# 780-00020_rev_1_pg1_Two_Axis_Stepper_Dri.net
KiCad netlist of a schematic drawn in Altium Designer
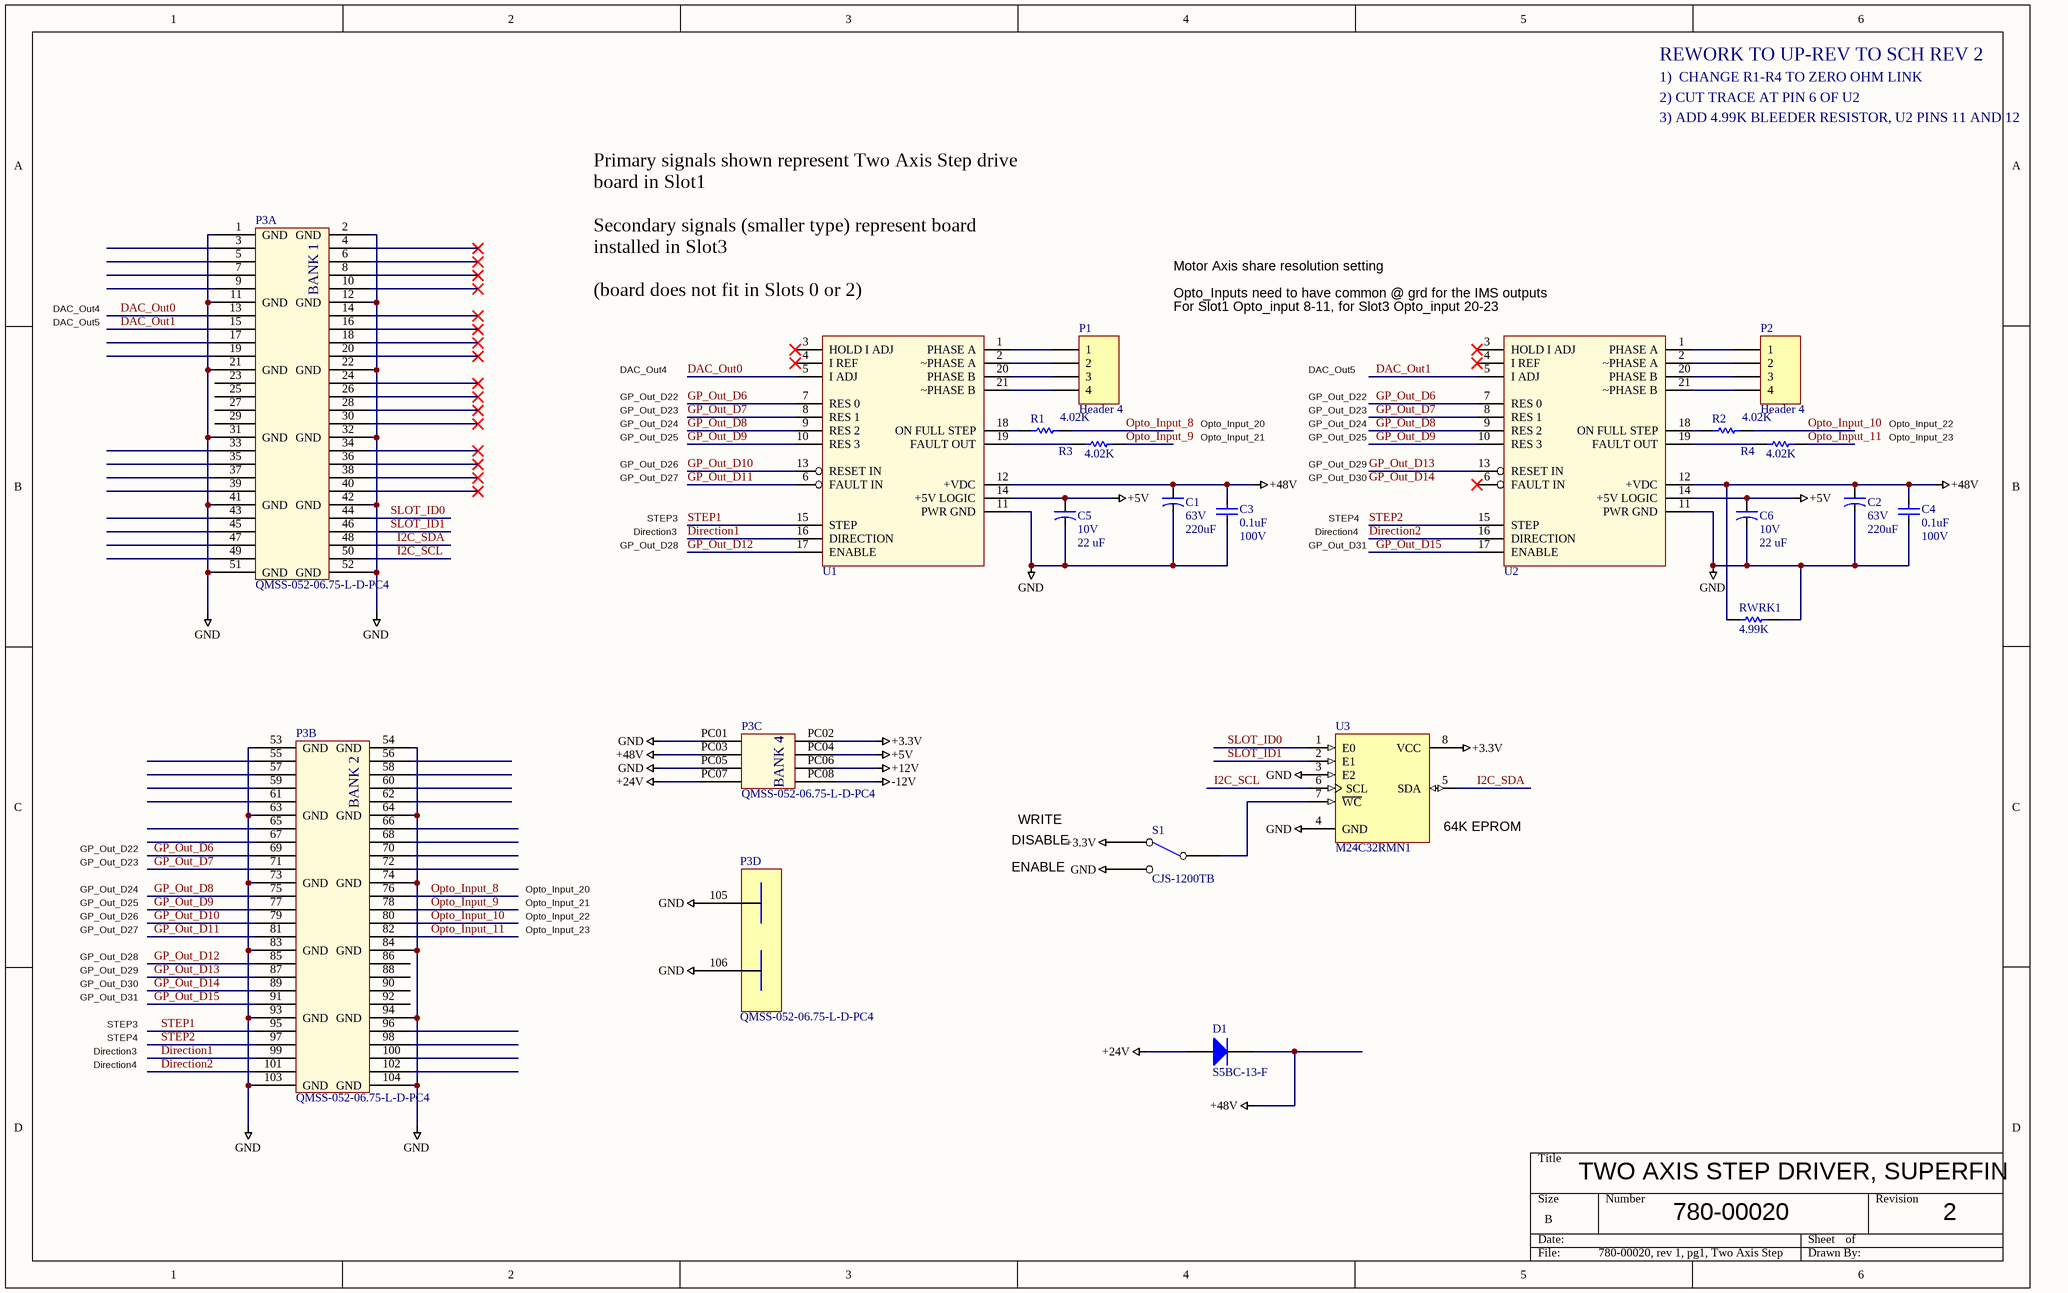
[diagram p0: 780-00020, rev 1, pg1, Two Axis Stepper Driver.SchDoc]

(export (version "E")
  (design (tool "Eeschema 10.0.6"))
  (components
    (comp (ref "C1")
      (value "63V")
      (footprint "CAP 220uF 63V")
      (description "CAP 220UF 63V ELECT MVH SMD")
      (fields (field (name "MANUFACTURER") "United Chemi-Con") (field (name "ALTIUM_VALUE") "220uF"))
      (libsource (lib "Richs Schematic Components") (part "Cap 220uF, 63V"))
    )
    (comp (ref "C2")
      (value "63V")
      (footprint "CAP 220uF 63V")
      (description "CAP 220UF 63V ELECT MVH SMD")
      (fields (field (name "MANUFACTURER") "United Chemi-Con") (field (name "ALTIUM_VALUE") "220uF"))
      (libsource (lib "Richs Schematic Components") (part "Cap 220uF, 63V"))
    )
    (comp (ref "C3")
      (value "100V")
      (footprint "SMD_0805")
      (description "Capacitor")
      (fields (field (name "MANUFACTURER") "TDK") (field (name "ALTIUM_VALUE") "0.1uF"))
      (libsource (lib "Richs Schematic Components") (part "Cap SMD"))
    )
    (comp (ref "C4")
      (value "100V")
      (footprint "SMD_0805")
      (description "Capacitor")
      (fields (field (name "MANUFACTURER") "TDK") (field (name "ALTIUM_VALUE") "0.1uF"))
      (libsource (lib "Richs Schematic Components") (part "Cap SMD"))
    )
    (comp (ref "C5")
      (value "10V")
      (footprint "SMD_CAP_3216")
      (description "outline 3.2mm x 1.6mm")
      (fields (field (name "MANUFACTURER") "AVX") (field (name "ALTIUM_VALUE") "22 uF"))
      (libsource (lib "Richs Schematic Components") (part "Cap Tant 16V"))
    )
    (comp (ref "C6")
      (value "10V")
      (footprint "SMD_CAP_3216")
      (description "outline 3.2mm x 1.6mm")
      (fields (field (name "MANUFACTURER") "AVX") (field (name "ALTIUM_VALUE") "22 uF"))
      (libsource (lib "Richs Schematic Components") (part "Cap Tant 16V"))
    )
    (comp (ref "D1")
      (value "S5BC-13-F")
      (footprint "SMC")
      (description "RECTIFIER GPP SMD 100V 5A SMC")
      (fields (field (name "MANUFACTURER") "Diodes Inc"))
      (libsource (lib "Miscellaneous Devices") (part "Diode"))
    )
    (comp (ref "P1")
      (value "Header 4")
      (footprint "HDR1X4 for IDC")
      (description "Header, 4-Pin")
      (libsource (lib "Richs Schematic Components") (part "Header 4"))
    )
    (comp (ref "P2")
      (value "Header 4")
      (footprint "HDR1X4 for IDC")
      (description "Header, 4-Pin")
      (libsource (lib "Richs Schematic Components") (part "Header 4"))
    )
    (comp (ref "P3")
      (value "QMSS-052-06.75-L-D-PC4")
      (footprint "QMS SMD PWR PINS - 104PIN")
      (description "SAMTEC QMSS W/PWR PINS")
      (fields (field (name "MANUFACTURER") "SAMTEC"))
      (libsource (lib "Richs Schematic Components") (part "QMSS-PC4-104 pin"))
    )
    (comp (ref "R1")
      (value "4.02K")
      (footprint "SMD_0805")
      (description "Resistor 0805")
      (fields (field (name "MANUFACTURER") "Vishay/Dale") (field (name "Comment") "Res 0805"))
      (libsource (lib "Richs Schematic Components") (part "Res SMD"))
    )
    (comp (ref "R2")
      (value "4.02K")
      (footprint "SMD_0805")
      (description "Resistor 0805")
      (fields (field (name "MANUFACTURER") "Vishay/Dale") (field (name "Comment") "Res 0805"))
      (libsource (lib "Richs Schematic Components") (part "Res SMD"))
    )
    (comp (ref "R3")
      (value "4.02K")
      (footprint "SMD_0805")
      (description "Resistor 0805")
      (fields (field (name "MANUFACTURER") "Vishay/Dale") (field (name "Comment") "Res 0805"))
      (libsource (lib "Richs Schematic Components") (part "Res SMD"))
    )
    (comp (ref "R4")
      (value "4.02K")
      (footprint "SMD_0805")
      (description "Resistor 0805")
      (fields (field (name "MANUFACTURER") "Vishay/Dale") (field (name "Comment") "Res 0805"))
      (libsource (lib "Richs Schematic Components") (part "Res SMD"))
    )
    (comp (ref "RWRK1")
      (value "4.99K")
      (footprint "AXIAL-0.4")
      (description "Resistor")
      (fields (field (name "Comment") "Res TH"))
      (libsource (lib "Richs Schematic Components") (part "Res TH"))
    )
    (comp (ref "S1")
      (value "CJS-1200TB")
      (footprint "CAS-120B")
      (fields (field (name "MANUFACTURER") "Copal Electronics"))
      (libsource (lib "JON_1_Library") (part "SW_SPDT_DOUG"))
    )
    (comp (ref "U1")
      (value "IM481H Plus")
      (footprint "IM481H Vertical")
      (description "Hybrid stepper motor driver")
      (libsource (lib "Richs Schematic Components") (part "IM481H Plus"))
    )
    (comp (ref "U2")
      (value "IM481H Plus")
      (footprint "IM481H Vertical")
      (description "Hybrid stepper motor driver")
      (libsource (lib "Richs Schematic Components") (part "IM481H Plus"))
    )
    (comp (ref "U3")
      (value "M24C32RMN1")
      (footprint "SOP8_N")
      (description "32 Kbit Serial I²C Bus EEPROM")
      (libsource (lib "ST Memory EEPROM Serial") (part "M24C32RMN1"))
    )
  )
  (nets
    (net (code "1") (name "+3.3V") (class "Default")
      (node (ref "P3") (pin "PC02") (pinfunction "PC02_PC02") (pintype "passive"))
      (node (ref "S1") (pin "3") (pinfunction "NC_3") (pintype "passive"))
      (node (ref "U3") (pin "8") (pinfunction "VCC_8") (pintype "power_in"))
    )
    (net (code "2") (name "+5V") (class "Default")
      (node (ref "C5") (pin "1") (pinfunction "1_1") (pintype "passive"))
      (node (ref "C6") (pin "1") (pinfunction "1_1") (pintype "passive"))
      (node (ref "P3") (pin "PC04") (pinfunction "PC04_PC04") (pintype "passive"))
      (node (ref "U1") (pin "14") (pinfunction "+5V_LOGIC_14") (pintype "passive"))
      (node (ref "U2") (pin "14") (pinfunction "+5V_LOGIC_14") (pintype "passive"))
    )
    (net (code "3") (name "+12V") (class "Default")
      (node (ref "P3") (pin "PC06") (pinfunction "PC06_PC06") (pintype "passive"))
    )
    (net (code "4") (name "+24V") (class "Default")
      (node (ref "D1") (pin "1") (pinfunction "A_1") (pintype "passive"))
      (node (ref "P3") (pin "PC07") (pinfunction "PC07_PC07") (pintype "passive"))
    )
    (net (code "5") (name "+48V") (class "Default")
      (node (ref "C1") (pin "1") (pinfunction "1_1") (pintype "passive"))
      (node (ref "C2") (pin "1") (pinfunction "1_1") (pintype "passive"))
      (node (ref "C3") (pin "2") (pinfunction "2_2") (pintype "passive"))
      (node (ref "C4") (pin "2") (pinfunction "2_2") (pintype "passive"))
      (node (ref "D1") (pin "2") (pinfunction "K_2") (pintype "passive"))
      (node (ref "P3") (pin "PC03") (pinfunction "PC03_PC03") (pintype "passive"))
      (node (ref "RWRK1") (pin "1") (pinfunction "1_1") (pintype "passive"))
      (node (ref "U1") (pin "12") (pinfunction "+VDC_12") (pintype "passive"))
      (node (ref "U2") (pin "12") (pinfunction "+VDC_12") (pintype "passive"))
    )
    (net (code "6") (name "-12V") (class "Default")
      (node (ref "P3") (pin "PC08") (pinfunction "PC08_PC08") (pintype "passive"))
    )
    (net (code "7") (name "/DAC_Out0") (class "Default")
      (node (ref "P3") (pin "13") (pinfunction "13_13") (pintype "passive"))
      (node (ref "U1") (pin "5") (pinfunction "I_ADJ_5") (pintype "passive"))
    )
    (net (code "8") (name "/DAC_Out1") (class "Default")
      (node (ref "P3") (pin "15") (pinfunction "15_15") (pintype "passive"))
      (node (ref "U2") (pin "5") (pinfunction "I_ADJ_5") (pintype "passive"))
    )
    (net (code "9") (name "/Direction1") (class "Default")
      (node (ref "P3") (pin "99") (pinfunction "99_99") (pintype "passive"))
      (node (ref "U1") (pin "16") (pinfunction "DIRECTION_16") (pintype "passive"))
    )
    (net (code "10") (name "/Direction2") (class "Default")
      (node (ref "P3") (pin "101") (pinfunction "101_101") (pintype "passive"))
      (node (ref "U2") (pin "16") (pinfunction "DIRECTION_16") (pintype "passive"))
    )
    (net (code "11") (name "/GP_Out_D6") (class "Default")
      (node (ref "P3") (pin "69") (pinfunction "69_69") (pintype "passive"))
      (node (ref "U1") (pin "7") (pinfunction "RES_0_7") (pintype "passive"))
      (node (ref "U2") (pin "7") (pinfunction "RES_0_7") (pintype "passive"))
    )
    (net (code "12") (name "/GP_Out_D7") (class "Default")
      (node (ref "P3") (pin "71") (pinfunction "71_71") (pintype "passive"))
      (node (ref "U1") (pin "8") (pinfunction "RES_1_8") (pintype "passive"))
      (node (ref "U2") (pin "8") (pinfunction "RES_1_8") (pintype "passive"))
    )
    (net (code "13") (name "/GP_Out_D8") (class "Default")
      (node (ref "P3") (pin "75") (pinfunction "75_75") (pintype "passive"))
      (node (ref "U1") (pin "9") (pinfunction "RES_2_9") (pintype "passive"))
      (node (ref "U2") (pin "9") (pinfunction "RES_2_9") (pintype "passive"))
    )
    (net (code "14") (name "/GP_Out_D9") (class "Default")
      (node (ref "P3") (pin "77") (pinfunction "77_77") (pintype "passive"))
      (node (ref "U1") (pin "10") (pinfunction "RES_3_10") (pintype "passive"))
      (node (ref "U2") (pin "10") (pinfunction "RES_3_10") (pintype "passive"))
    )
    (net (code "15") (name "/GP_Out_D10") (class "Default")
      (node (ref "P3") (pin "79") (pinfunction "79_79") (pintype "passive"))
      (node (ref "U1") (pin "13") (pinfunction "RESET_IN_13") (pintype "passive"))
    )
    (net (code "16") (name "/GP_Out_D11") (class "Default")
      (node (ref "P3") (pin "81") (pinfunction "81_81") (pintype "passive"))
      (node (ref "U1") (pin "6") (pinfunction "FAULT_IN_6") (pintype "passive"))
    )
    (net (code "17") (name "/GP_Out_D12") (class "Default")
      (node (ref "P3") (pin "85") (pinfunction "85_85") (pintype "passive"))
      (node (ref "U1") (pin "17") (pinfunction "ENABLE_17") (pintype "passive"))
    )
    (net (code "18") (name "/GP_Out_D13") (class "Default")
      (node (ref "P3") (pin "87") (pinfunction "87_87") (pintype "passive"))
      (node (ref "U2") (pin "13") (pinfunction "RESET_IN_13") (pintype "passive"))
    )
    (net (code "19") (name "/GP_Out_D14") (class "Default")
      (node (ref "P3") (pin "89") (pinfunction "89_89") (pintype "passive"))
    )
    (net (code "20") (name "/GP_Out_D15") (class "Default")
      (node (ref "P3") (pin "91") (pinfunction "91_91") (pintype "passive"))
      (node (ref "U2") (pin "17") (pinfunction "ENABLE_17") (pintype "passive"))
    )
    (net (code "21") (name "/I2C_SCL") (class "Default")
      (node (ref "P3") (pin "50") (pinfunction "50_50") (pintype "passive"))
      (node (ref "U3") (pin "6") (pinfunction "SCL_6") (pintype "input"))
    )
    (net (code "22") (name "/I2C_SDA") (class "Default")
      (node (ref "P3") (pin "48") (pinfunction "48_48") (pintype "passive"))
      (node (ref "U3") (pin "5") (pinfunction "SDA_5") (pintype "bidirectional"))
    )
    (net (code "23") (name "/Opto_Input_8") (class "Default")
      (node (ref "P3") (pin "76") (pinfunction "76_76") (pintype "passive"))
      (node (ref "R1") (pin "2") (pinfunction "2_2") (pintype "passive"))
    )
    (net (code "24") (name "/Opto_Input_9") (class "Default")
      (node (ref "P3") (pin "78") (pinfunction "78_78") (pintype "passive"))
      (node (ref "R3") (pin "2") (pinfunction "2_2") (pintype "passive"))
    )
    (net (code "25") (name "/Opto_Input_10") (class "Default")
      (node (ref "P3") (pin "80") (pinfunction "80_80") (pintype "passive"))
      (node (ref "R2") (pin "2") (pinfunction "2_2") (pintype "passive"))
    )
    (net (code "26") (name "/Opto_Input_11") (class "Default")
      (node (ref "P3") (pin "82") (pinfunction "82_82") (pintype "passive"))
      (node (ref "R4") (pin "2") (pinfunction "2_2") (pintype "passive"))
    )
    (net (code "27") (name "/SLOT_ID0") (class "Default")
      (node (ref "P3") (pin "44") (pinfunction "44_44") (pintype "passive"))
      (node (ref "U3") (pin "1") (pinfunction "E0_1") (pintype "input"))
    )
    (net (code "28") (name "/SLOT_ID1") (class "Default")
      (node (ref "P3") (pin "46") (pinfunction "46_46") (pintype "passive"))
      (node (ref "U3") (pin "2") (pinfunction "E1_2") (pintype "input"))
    )
    (net (code "29") (name "/STEP1") (class "Default")
      (node (ref "P3") (pin "95") (pinfunction "95_95") (pintype "passive"))
      (node (ref "U1") (pin "15") (pinfunction "STEP_15") (pintype "passive"))
    )
    (net (code "30") (name "/STEP2") (class "Default")
      (node (ref "P3") (pin "97") (pinfunction "97_97") (pintype "passive"))
      (node (ref "U2") (pin "15") (pinfunction "STEP_15") (pintype "passive"))
    )
    (net (code "31") (name "GND") (class "Default")
      (node (ref "C1") (pin "2") (pinfunction "2_2") (pintype "passive"))
      (node (ref "C2") (pin "2") (pinfunction "2_2") (pintype "passive"))
      (node (ref "C3") (pin "1") (pinfunction "1_1") (pintype "passive"))
      (node (ref "C4") (pin "1") (pinfunction "1_1") (pintype "passive"))
      (node (ref "C5") (pin "2") (pinfunction "2_2") (pintype "passive"))
      (node (ref "C6") (pin "2") (pinfunction "2_2") (pintype "passive"))
      (node (ref "P3") (pin "1") (pinfunction "GND_1") (pintype "passive"))
      (node (ref "P3") (pin "103") (pinfunction "GND_103") (pintype "passive"))
      (node (ref "P3") (pin "104") (pinfunction "GND_104") (pintype "passive"))
      (node (ref "P3") (pin "105") (pinfunction "GND_105") (pintype "passive"))
      (node (ref "P3") (pin "106") (pinfunction "GND_106") (pintype "passive"))
      (node (ref "P3") (pin "11") (pinfunction "GND_11") (pintype "passive"))
      (node (ref "P3") (pin "12") (pinfunction "GND_12") (pintype "passive"))
      (node (ref "P3") (pin "2") (pinfunction "GND_2") (pintype "passive"))
      (node (ref "P3") (pin "21") (pinfunction "GND_21") (pintype "passive"))
      (node (ref "P3") (pin "22") (pinfunction "GND_22") (pintype "passive"))
      (node (ref "P3") (pin "31") (pinfunction "GND_31") (pintype "passive"))
      (node (ref "P3") (pin "32") (pinfunction "GND_32") (pintype "passive"))
      (node (ref "P3") (pin "41") (pinfunction "GND_41") (pintype "passive"))
      (node (ref "P3") (pin "42") (pinfunction "GND_42") (pintype "passive"))
      (node (ref "P3") (pin "51") (pinfunction "GND_51") (pintype "passive"))
      (node (ref "P3") (pin "52") (pinfunction "GND_52") (pintype "passive"))
      (node (ref "P3") (pin "53") (pinfunction "GND_53") (pintype "passive"))
      (node (ref "P3") (pin "54") (pinfunction "GND_54") (pintype "passive"))
      (node (ref "P3") (pin "63") (pinfunction "GND_63") (pintype "passive"))
      (node (ref "P3") (pin "64") (pinfunction "GND_64") (pintype "passive"))
      (node (ref "P3") (pin "73") (pinfunction "GND_73") (pintype "passive"))
      (node (ref "P3") (pin "74") (pinfunction "GND_74") (pintype "passive"))
      (node (ref "P3") (pin "83") (pinfunction "GND_83") (pintype "passive"))
      (node (ref "P3") (pin "84") (pinfunction "GND_84") (pintype "passive"))
      (node (ref "P3") (pin "93") (pinfunction "GND_93") (pintype "passive"))
      (node (ref "P3") (pin "94") (pinfunction "GND_94") (pintype "passive"))
      (node (ref "P3") (pin "PC01") (pinfunction "PC01_PC01") (pintype "passive"))
      (node (ref "P3") (pin "PC05") (pinfunction "PC05_PC05") (pintype "passive"))
      (node (ref "RWRK1") (pin "2") (pinfunction "2_2") (pintype "passive"))
      (node (ref "S1") (pin "1") (pinfunction "NO_1") (pintype "passive"))
      (node (ref "U1") (pin "11") (pinfunction "PWR_GND_11") (pintype "passive"))
      (node (ref "U2") (pin "11") (pinfunction "PWR_GND_11") (pintype "passive"))
      (node (ref "U3") (pin "3") (pinfunction "E2_3") (pintype "input"))
      (node (ref "U3") (pin "4") (pinfunction "GND_4") (pintype "power_in"))
    )
    (net (code "32") (name "Net-(S1-COM)") (class "Default")
      (node (ref "S1") (pin "2") (pinfunction "COM_2") (pintype "passive"))
      (node (ref "U3") (pin "7") (pinfunction "~{WC}_7") (pintype "input"))
    )
    (net (code "33") (name "Net-(U1-FAULT_OUT)") (class "Default")
      (node (ref "R3") (pin "1") (pinfunction "1_1") (pintype "passive"))
      (node (ref "U1") (pin "19") (pinfunction "FAULT_OUT_19") (pintype "passive"))
    )
    (net (code "34") (name "Net-(U1-ON_FULL_STEP)") (class "Default")
      (node (ref "R1") (pin "1") (pinfunction "1_1") (pintype "passive"))
      (node (ref "U1") (pin "18") (pinfunction "ON_FULL_STEP_18") (pintype "passive"))
    )
    (net (code "35") (name "Net-(U1-PHASE_A)") (class "Default")
      (node (ref "P1") (pin "1") (pinfunction "1_1") (pintype "passive"))
      (node (ref "U1") (pin "1") (pinfunction "PHASE_A_1") (pintype "passive"))
    )
    (net (code "36") (name "Net-(U1-PHASE_B)") (class "Default")
      (node (ref "P1") (pin "3") (pinfunction "3_3") (pintype "passive"))
      (node (ref "U1") (pin "20") (pinfunction "PHASE_B_20") (pintype "passive"))
    )
    (net (code "37") (name "Net-(U1-~PHASE_A)") (class "Default")
      (node (ref "P1") (pin "2") (pinfunction "2_2") (pintype "passive"))
      (node (ref "U1") (pin "2") (pinfunction "~PHASE_A_2") (pintype "passive"))
    )
    (net (code "38") (name "Net-(U1-~PHASE_B)") (class "Default")
      (node (ref "P1") (pin "4") (pinfunction "4_4") (pintype "passive"))
      (node (ref "U1") (pin "21") (pinfunction "~PHASE_B_21") (pintype "passive"))
    )
    (net (code "39") (name "Net-(U2-FAULT_OUT)") (class "Default")
      (node (ref "R4") (pin "1") (pinfunction "1_1") (pintype "passive"))
      (node (ref "U2") (pin "19") (pinfunction "FAULT_OUT_19") (pintype "passive"))
    )
    (net (code "40") (name "Net-(U2-ON_FULL_STEP)") (class "Default")
      (node (ref "R2") (pin "1") (pinfunction "1_1") (pintype "passive"))
      (node (ref "U2") (pin "18") (pinfunction "ON_FULL_STEP_18") (pintype "passive"))
    )
    (net (code "41") (name "Net-(U2-PHASE_A)") (class "Default")
      (node (ref "P2") (pin "1") (pinfunction "1_1") (pintype "passive"))
      (node (ref "U2") (pin "1") (pinfunction "PHASE_A_1") (pintype "passive"))
    )
    (net (code "42") (name "Net-(U2-PHASE_B)") (class "Default")
      (node (ref "P2") (pin "3") (pinfunction "3_3") (pintype "passive"))
      (node (ref "U2") (pin "20") (pinfunction "PHASE_B_20") (pintype "passive"))
    )
    (net (code "43") (name "Net-(U2-~PHASE_A)") (class "Default")
      (node (ref "P2") (pin "2") (pinfunction "2_2") (pintype "passive"))
      (node (ref "U2") (pin "2") (pinfunction "~PHASE_A_2") (pintype "passive"))
    )
    (net (code "44") (name "Net-(U2-~PHASE_B)") (class "Default")
      (node (ref "P2") (pin "4") (pinfunction "4_4") (pintype "passive"))
      (node (ref "U2") (pin "21") (pinfunction "~PHASE_B_21") (pintype "passive"))
    )
    (net (code "45") (name "unconnected-(P3-Pad3)") (class "Default")
      (node (ref "P3") (pin "3") (pinfunction "3_3") (pintype "passive"))
    )
    (net (code "46") (name "unconnected-(P3-Pad4)") (class "Default")
      (node (ref "P3") (pin "4") (pinfunction "4_4") (pintype "passive+no_connect"))
    )
    (net (code "47") (name "unconnected-(P3-Pad5)") (class "Default")
      (node (ref "P3") (pin "5") (pinfunction "5_5") (pintype "passive"))
    )
    (net (code "48") (name "unconnected-(P3-Pad6)") (class "Default")
      (node (ref "P3") (pin "6") (pinfunction "6_6") (pintype "passive+no_connect"))
    )
    (net (code "49") (name "unconnected-(P3-Pad7)") (class "Default")
      (node (ref "P3") (pin "7") (pinfunction "7_7") (pintype "passive"))
    )
    (net (code "50") (name "unconnected-(P3-Pad8)") (class "Default")
      (node (ref "P3") (pin "8") (pinfunction "8_8") (pintype "passive+no_connect"))
    )
    (net (code "51") (name "unconnected-(P3-Pad9)") (class "Default")
      (node (ref "P3") (pin "9") (pinfunction "9_9") (pintype "passive"))
    )
    (net (code "52") (name "unconnected-(P3-Pad10)") (class "Default")
      (node (ref "P3") (pin "10") (pinfunction "10_10") (pintype "passive+no_connect"))
    )
    (net (code "53") (name "unconnected-(P3-Pad14)") (class "Default")
      (node (ref "P3") (pin "14") (pinfunction "14_14") (pintype "passive+no_connect"))
    )
    (net (code "54") (name "unconnected-(P3-Pad16)") (class "Default")
      (node (ref "P3") (pin "16") (pinfunction "16_16") (pintype "passive+no_connect"))
    )
    (net (code "55") (name "unconnected-(P3-Pad17)") (class "Default")
      (node (ref "P3") (pin "17") (pinfunction "17_17") (pintype "passive"))
    )
    (net (code "56") (name "unconnected-(P3-Pad18)") (class "Default")
      (node (ref "P3") (pin "18") (pinfunction "18_18") (pintype "passive+no_connect"))
    )
    (net (code "57") (name "unconnected-(P3-Pad19)") (class "Default")
      (node (ref "P3") (pin "19") (pinfunction "19_19") (pintype "passive"))
    )
    (net (code "58") (name "unconnected-(P3-Pad20)") (class "Default")
      (node (ref "P3") (pin "20") (pinfunction "20_20") (pintype "passive+no_connect"))
    )
    (net (code "59") (name "unconnected-(P3-Pad23)") (class "Default")
      (node (ref "P3") (pin "23") (pinfunction "23_23") (pintype "passive"))
    )
    (net (code "60") (name "unconnected-(P3-Pad24)") (class "Default")
      (node (ref "P3") (pin "24") (pinfunction "24_24") (pintype "passive+no_connect"))
    )
    (net (code "61") (name "unconnected-(P3-Pad25)") (class "Default")
      (node (ref "P3") (pin "25") (pinfunction "25_25") (pintype "passive"))
    )
    (net (code "62") (name "unconnected-(P3-Pad26)") (class "Default")
      (node (ref "P3") (pin "26") (pinfunction "26_26") (pintype "passive+no_connect"))
    )
    (net (code "63") (name "unconnected-(P3-Pad27)") (class "Default")
      (node (ref "P3") (pin "27") (pinfunction "27_27") (pintype "passive"))
    )
    (net (code "64") (name "unconnected-(P3-Pad28)") (class "Default")
      (node (ref "P3") (pin "28") (pinfunction "28_28") (pintype "passive+no_connect"))
    )
    (net (code "65") (name "unconnected-(P3-Pad29)") (class "Default")
      (node (ref "P3") (pin "29") (pinfunction "29_29") (pintype "passive"))
    )
    (net (code "66") (name "unconnected-(P3-Pad30)") (class "Default")
      (node (ref "P3") (pin "30") (pinfunction "30_30") (pintype "passive+no_connect"))
    )
    (net (code "67") (name "unconnected-(P3-Pad33)") (class "Default")
      (node (ref "P3") (pin "33") (pinfunction "33_33") (pintype "passive"))
    )
    (net (code "68") (name "unconnected-(P3-Pad34)") (class "Default")
      (node (ref "P3") (pin "34") (pinfunction "34_34") (pintype "passive+no_connect"))
    )
    (net (code "69") (name "unconnected-(P3-Pad35)") (class "Default")
      (node (ref "P3") (pin "35") (pinfunction "35_35") (pintype "passive"))
    )
    (net (code "70") (name "unconnected-(P3-Pad36)") (class "Default")
      (node (ref "P3") (pin "36") (pinfunction "36_36") (pintype "passive+no_connect"))
    )
    (net (code "71") (name "unconnected-(P3-Pad37)") (class "Default")
      (node (ref "P3") (pin "37") (pinfunction "37_37") (pintype "passive"))
    )
    (net (code "72") (name "unconnected-(P3-Pad38)") (class "Default")
      (node (ref "P3") (pin "38") (pinfunction "38_38") (pintype "passive+no_connect"))
    )
    (net (code "73") (name "unconnected-(P3-Pad39)") (class "Default")
      (node (ref "P3") (pin "39") (pinfunction "39_39") (pintype "passive"))
    )
    (net (code "74") (name "unconnected-(P3-Pad40)") (class "Default")
      (node (ref "P3") (pin "40") (pinfunction "40_40") (pintype "passive+no_connect"))
    )
    (net (code "75") (name "unconnected-(P3-Pad43)") (class "Default")
      (node (ref "P3") (pin "43") (pinfunction "43_43") (pintype "passive"))
    )
    (net (code "76") (name "unconnected-(P3-Pad45)") (class "Default")
      (node (ref "P3") (pin "45") (pinfunction "45_45") (pintype "passive"))
    )
    (net (code "77") (name "unconnected-(P3-Pad47)") (class "Default")
      (node (ref "P3") (pin "47") (pinfunction "47_47") (pintype "passive"))
    )
    (net (code "78") (name "unconnected-(P3-Pad49)") (class "Default")
      (node (ref "P3") (pin "49") (pinfunction "49_49") (pintype "passive"))
    )
    (net (code "79") (name "unconnected-(P3-Pad55)") (class "Default")
      (node (ref "P3") (pin "55") (pinfunction "55_55") (pintype "passive"))
    )
    (net (code "80") (name "unconnected-(P3-Pad56)") (class "Default")
      (node (ref "P3") (pin "56") (pinfunction "56_56") (pintype "passive"))
    )
    (net (code "81") (name "unconnected-(P3-Pad57)") (class "Default")
      (node (ref "P3") (pin "57") (pinfunction "57_57") (pintype "passive"))
    )
    (net (code "82") (name "unconnected-(P3-Pad58)") (class "Default")
      (node (ref "P3") (pin "58") (pinfunction "58_58") (pintype "passive"))
    )
    (net (code "83") (name "unconnected-(P3-Pad59)") (class "Default")
      (node (ref "P3") (pin "59") (pinfunction "59_59") (pintype "passive"))
    )
    (net (code "84") (name "unconnected-(P3-Pad60)") (class "Default")
      (node (ref "P3") (pin "60") (pinfunction "60_60") (pintype "passive"))
    )
    (net (code "85") (name "unconnected-(P3-Pad61)") (class "Default")
      (node (ref "P3") (pin "61") (pinfunction "61_61") (pintype "passive"))
    )
    (net (code "86") (name "unconnected-(P3-Pad62)") (class "Default")
      (node (ref "P3") (pin "62") (pinfunction "62_62") (pintype "passive"))
    )
    (net (code "87") (name "unconnected-(P3-Pad65)") (class "Default")
      (node (ref "P3") (pin "65") (pinfunction "65_65") (pintype "passive"))
    )
    (net (code "88") (name "unconnected-(P3-Pad66)") (class "Default")
      (node (ref "P3") (pin "66") (pinfunction "66_66") (pintype "passive"))
    )
    (net (code "89") (name "unconnected-(P3-Pad67)") (class "Default")
      (node (ref "P3") (pin "67") (pinfunction "67_67") (pintype "passive"))
    )
    (net (code "90") (name "unconnected-(P3-Pad68)") (class "Default")
      (node (ref "P3") (pin "68") (pinfunction "68_68") (pintype "passive"))
    )
    (net (code "91") (name "unconnected-(P3-Pad70)") (class "Default")
      (node (ref "P3") (pin "70") (pinfunction "70_70") (pintype "passive"))
    )
    (net (code "92") (name "unconnected-(P3-Pad72)") (class "Default")
      (node (ref "P3") (pin "72") (pinfunction "72_72") (pintype "passive"))
    )
    (net (code "93") (name "unconnected-(P3-Pad86)") (class "Default")
      (node (ref "P3") (pin "86") (pinfunction "86_86") (pintype "passive"))
    )
    (net (code "94") (name "unconnected-(P3-Pad88)") (class "Default")
      (node (ref "P3") (pin "88") (pinfunction "88_88") (pintype "passive"))
    )
    (net (code "95") (name "unconnected-(P3-Pad90)") (class "Default")
      (node (ref "P3") (pin "90") (pinfunction "90_90") (pintype "passive"))
    )
    (net (code "96") (name "unconnected-(P3-Pad92)") (class "Default")
      (node (ref "P3") (pin "92") (pinfunction "92_92") (pintype "passive"))
    )
    (net (code "97") (name "unconnected-(P3-Pad96)") (class "Default")
      (node (ref "P3") (pin "96") (pinfunction "96_96") (pintype "passive"))
    )
    (net (code "98") (name "unconnected-(P3-Pad98)") (class "Default")
      (node (ref "P3") (pin "98") (pinfunction "98_98") (pintype "passive"))
    )
    (net (code "99") (name "unconnected-(P3-Pad100)") (class "Default")
      (node (ref "P3") (pin "100") (pinfunction "100_100") (pintype "passive"))
    )
    (net (code "100") (name "unconnected-(P3-Pad102)") (class "Default")
      (node (ref "P3") (pin "102") (pinfunction "102_102") (pintype "passive"))
    )
    (net (code "101") (name "unconnected-(U1-HOLD_I_ADJ-Pad3)") (class "Default")
      (node (ref "U1") (pin "3") (pinfunction "HOLD_I_ADJ_3") (pintype "passive+no_connect"))
    )
    (net (code "102") (name "unconnected-(U1-I_REF-Pad4)") (class "Default")
      (node (ref "U1") (pin "4") (pinfunction "I_REF_4") (pintype "passive+no_connect"))
    )
    (net (code "103") (name "unconnected-(U2-FAULT_IN-Pad6)") (class "Default")
      (node (ref "U2") (pin "6") (pinfunction "FAULT_IN_6") (pintype "passive+no_connect"))
    )
    (net (code "104") (name "unconnected-(U2-HOLD_I_ADJ-Pad3)") (class "Default")
      (node (ref "U2") (pin "3") (pinfunction "HOLD_I_ADJ_3") (pintype "passive+no_connect"))
    )
    (net (code "105") (name "unconnected-(U2-I_REF-Pad4)") (class "Default")
      (node (ref "U2") (pin "4") (pinfunction "I_REF_4") (pintype "passive+no_connect"))
    )
  )
)
